# contactor_connectors.net
KiCad netlist of a schematic drawn in Altium Designer
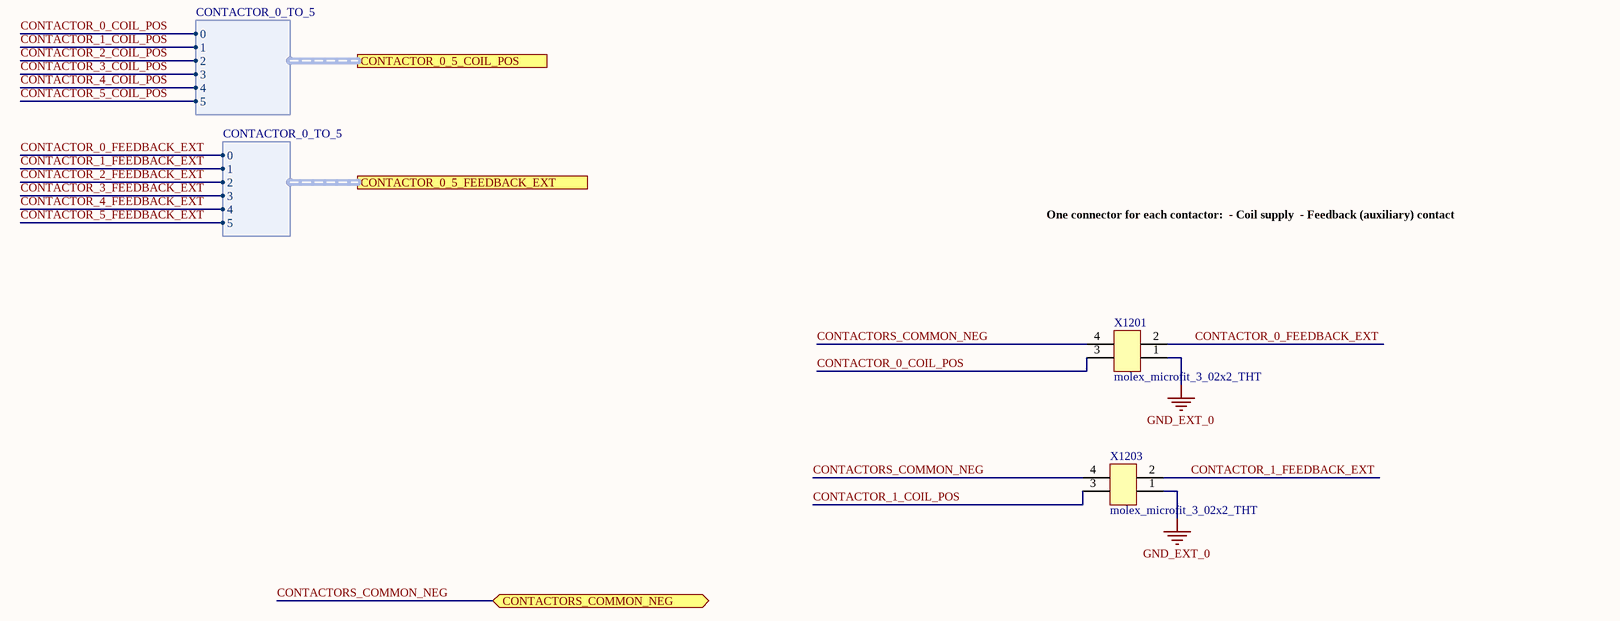
[diagram p0: contactor_connectors.SchDoc]

(export (version "E")
  (design (tool "Eeschema 10.0.6"))
  (components
    (comp (ref "X1201")
      (value "molex_microfit_3_02x2_THT")
      (footprint "MOLEX_MICROFIT_02x2_THT")
      (fields (field (name "MANUFACTURER") "Molex"))
      (libsource (lib "OE750") (part "X2x2"))
    )
    (comp (ref "X1203")
      (value "molex_microfit_3_02x2_THT")
      (footprint "MOLEX_MICROFIT_02x2_THT")
      (fields (field (name "MANUFACTURER") "Molex"))
      (libsource (lib "OE750") (part "X2x2"))
    )
  )
  (nets
    (net (code "2") (name "/CONTACTORS_COMMON_NEG") (class "Default")
      (node (ref "X1201") (pin "4") (pintype "passive"))
      (node (ref "X1203") (pin "4") (pintype "passive"))
    )
    (net (code "3") (name "/CONTACTOR_0_COIL_POS") (class "Default")
      (node (ref "X1201") (pin "3") (pintype "passive"))
    )
    (net (code "4") (name "/CONTACTOR_0_FEEDBACK_EXT") (class "Default")
      (node (ref "X1201") (pin "2") (pintype "passive"))
    )
    (net (code "5") (name "/CONTACTOR_1_COIL_POS") (class "Default")
      (node (ref "X1203") (pin "3") (pintype "passive"))
    )
    (net (code "6") (name "/CONTACTOR_1_FEEDBACK_EXT") (class "Default")
      (node (ref "X1203") (pin "2") (pintype "passive"))
    )
    (net (code "16") (name "GND_EXT_0") (class "Default")
      (node (ref "X1201") (pin "1") (pintype "passive"))
      (node (ref "X1203") (pin "1") (pintype "passive"))
    )
  )
)
